# pwr.net
KiCad netlist of a schematic drawn in EAGLE
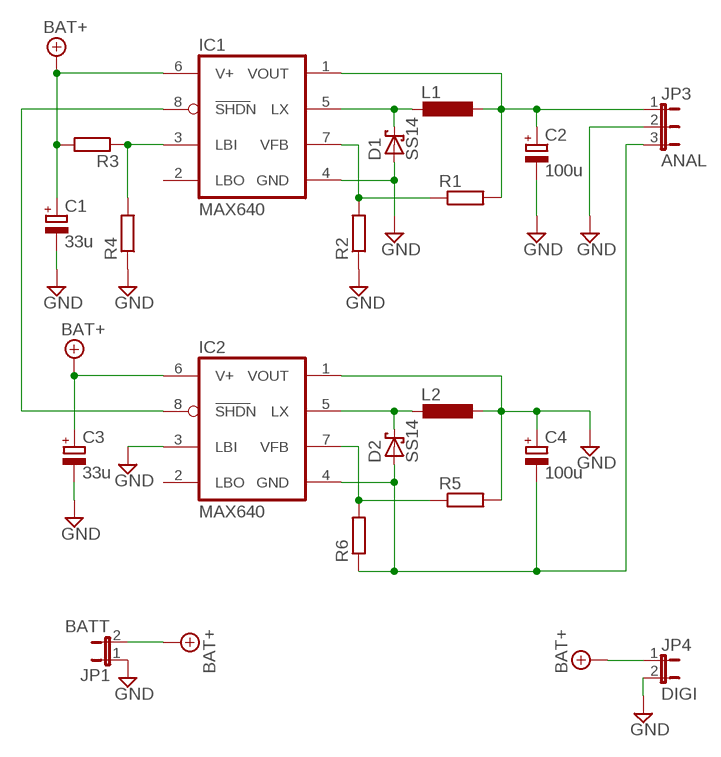
[diagram p0: schematic, sheet 1]

(export (version "E")
  (design (tool "Eeschema 10.0.6"))
  (components
    (comp (ref "C1")
      (value "33u")
      (footprint "eagle-import:SMC_C")
      (libsource (lib "eagle-import") (part "CPOL-EUSMCC"))
    )
    (comp (ref "C2")
      (value "100u")
      (footprint "eagle-import:SMC_C")
      (libsource (lib "eagle-import") (part "CPOL-EUSMCC"))
    )
    (comp (ref "C3")
      (value "33u")
      (footprint "eagle-import:SMC_C")
      (libsource (lib "eagle-import") (part "CPOL-EUSMCC"))
    )
    (comp (ref "C4")
      (value "100u")
      (footprint "eagle-import:SMC_C")
      (libsource (lib "eagle-import") (part "CPOL-EUSMCC"))
    )
    (comp (ref "D1")
      (value "SS14")
      (footprint "eagle-import:SMA")
      (libsource (lib "eagle-import") (part "SS14"))
    )
    (comp (ref "D2")
      (value "SS14")
      (footprint "eagle-import:SMA")
      (libsource (lib "eagle-import") (part "SS14"))
    )
    (comp (ref "IC1")
      (value "MAX640")
      (footprint "eagle-import:SO08")
      (libsource (lib "eagle-import") (part "MAX640"))
    )
    (comp (ref "IC2")
      (value "MAX640")
      (footprint "eagle-import:SO08")
      (libsource (lib "eagle-import") (part "MAX640"))
    )
    (comp (ref "JP1")
      (value "BATT")
      (footprint "eagle-import:JP1")
      (libsource (lib "eagle-import") (part "JP1E"))
    )
    (comp (ref "JP3")
      (value "ANAL")
      (footprint "eagle-import:JP2")
      (libsource (lib "eagle-import") (part "JP2E"))
    )
    (comp (ref "JP4")
      (value "DIGI")
      (footprint "eagle-import:JP1")
      (libsource (lib "eagle-import") (part "JP1E"))
    )
    (comp (ref "L1")
      (value "L-EUWE-TPC")
      (footprint "eagle-import:POWER-CHOKE_WE-TPC")
      (libsource (lib "eagle-import") (part "L-EUWE-TPC"))
    )
    (comp (ref "L2")
      (value "L-EUWE-TPC")
      (footprint "eagle-import:POWER-CHOKE_WE-TPC")
      (libsource (lib "eagle-import") (part "L-EUWE-TPC"))
    )
    (comp (ref "R1")
      (value "R-EU_R0805")
      (footprint "eagle-import:R0805")
      (libsource (lib "eagle-import") (part "R-EU_R0805"))
    )
    (comp (ref "R2")
      (value "R-EU_R0805")
      (footprint "eagle-import:R0805")
      (libsource (lib "eagle-import") (part "R-EU_R0805"))
    )
    (comp (ref "R3")
      (value "R-EU_R0805")
      (footprint "eagle-import:R0805")
      (libsource (lib "eagle-import") (part "R-EU_R0805"))
    )
    (comp (ref "R4")
      (value "R-EU_R0805")
      (footprint "eagle-import:R0805")
      (libsource (lib "eagle-import") (part "R-EU_R0805"))
    )
    (comp (ref "R5")
      (value "R-EU_R0805")
      (footprint "eagle-import:R0805")
      (libsource (lib "eagle-import") (part "R-EU_R0805"))
    )
    (comp (ref "R6")
      (value "R-EU_R0805")
      (footprint "eagle-import:R0805")
      (libsource (lib "eagle-import") (part "R-EU_R0805"))
    )
  )
  (nets
    (net (code "1") (name "BAT+") (class "Default")
      (node (ref "C1") (pin "+") (pinfunction "+_+") (pintype "passive"))
      (node (ref "C3") (pin "+") (pinfunction "+_+") (pintype "passive"))
      (node (ref "IC1") (pin "6") (pinfunction "V+_6") (pintype "power_in"))
      (node (ref "IC2") (pin "6") (pinfunction "V+_6") (pintype "power_in"))
      (node (ref "JP1") (pin "2") (pinfunction "2_2") (pintype "passive"))
      (node (ref "JP4") (pin "1") (pinfunction "1_1") (pintype "passive"))
      (node (ref "R3") (pin "2") (pinfunction "2_2") (pintype "passive"))
    )
    (net (code "2") (name "GND") (class "Default")
      (node (ref "C1") (pin "-") (pinfunction "-_-") (pintype "passive"))
      (node (ref "C2") (pin "-") (pinfunction "-_-") (pintype "passive"))
      (node (ref "C3") (pin "-") (pinfunction "-_-") (pintype "passive"))
      (node (ref "C4") (pin "+") (pinfunction "+_+") (pintype "passive"))
      (node (ref "D1") (pin "A") (pinfunction "A_A") (pintype "passive"))
      (node (ref "IC1") (pin "4") (pinfunction "GND_4") (pintype "power_in"))
      (node (ref "IC2") (pin "1") (pinfunction "VOUT_1") (pintype "output"))
      (node (ref "IC2") (pin "3") (pinfunction "LBI_3") (pintype "input"))
      (node (ref "JP1") (pin "1") (pinfunction "1_1") (pintype "passive"))
      (node (ref "JP3") (pin "2") (pinfunction "2_2") (pintype "passive"))
      (node (ref "JP4") (pin "2") (pinfunction "2_2") (pintype "passive"))
      (node (ref "L2") (pin "1") (pinfunction "1_1") (pintype "passive"))
      (node (ref "R2") (pin "1") (pinfunction "1_1") (pintype "passive"))
      (node (ref "R4") (pin "1") (pinfunction "1_1") (pintype "passive"))
      (node (ref "R5") (pin "2") (pinfunction "2_2") (pintype "passive"))
    )
    (net (code "3") (name "Net-(IC1-LBI)") (class "Default")
      (node (ref "IC1") (pin "3") (pinfunction "LBI_3") (pintype "input"))
      (node (ref "R3") (pin "1") (pinfunction "1_1") (pintype "passive"))
      (node (ref "R4") (pin "2") (pinfunction "2_2") (pintype "passive"))
    )
    (net (code "4") (name "Net-(IC1-LX)") (class "Default")
      (node (ref "D1") (pin "C") (pinfunction "C_C") (pintype "passive"))
      (node (ref "IC1") (pin "5") (pinfunction "LX_5") (pintype "output"))
      (node (ref "L1") (pin "2") (pinfunction "2_2") (pintype "passive"))
    )
    (net (code "5") (name "Net-(IC1-SHDN)") (class "Default")
      (node (ref "IC1") (pin "8") (pinfunction "SHDN_8") (pintype "input"))
      (node (ref "IC2") (pin "8") (pinfunction "SHDN_8") (pintype "input"))
    )
    (net (code "6") (name "Net-(IC1-VFB)") (class "Default")
      (node (ref "IC1") (pin "7") (pinfunction "VFB_7") (pintype "output"))
      (node (ref "R1") (pin "1") (pinfunction "1_1") (pintype "passive"))
      (node (ref "R2") (pin "2") (pinfunction "2_2") (pintype "passive"))
    )
    (net (code "7") (name "Net-(IC1-VOUT)") (class "Default")
      (node (ref "C2") (pin "+") (pinfunction "+_+") (pintype "passive"))
      (node (ref "IC1") (pin "1") (pinfunction "VOUT_1") (pintype "output"))
      (node (ref "JP3") (pin "1") (pinfunction "1_1") (pintype "passive"))
      (node (ref "L1") (pin "1") (pinfunction "1_1") (pintype "passive"))
      (node (ref "R1") (pin "2") (pinfunction "2_2") (pintype "passive"))
    )
    (net (code "8") (name "Net-(IC2-GND)") (class "Default")
      (node (ref "C4") (pin "-") (pinfunction "-_-") (pintype "passive"))
      (node (ref "D2") (pin "A") (pinfunction "A_A") (pintype "passive"))
      (node (ref "IC2") (pin "4") (pinfunction "GND_4") (pintype "power_in"))
      (node (ref "JP3") (pin "3") (pinfunction "3_3") (pintype "passive"))
      (node (ref "R6") (pin "1") (pinfunction "1_1") (pintype "passive"))
    )
    (net (code "9") (name "Net-(IC2-LX)") (class "Default")
      (node (ref "D2") (pin "C") (pinfunction "C_C") (pintype "passive"))
      (node (ref "IC2") (pin "5") (pinfunction "LX_5") (pintype "output"))
      (node (ref "L2") (pin "2") (pinfunction "2_2") (pintype "passive"))
    )
    (net (code "10") (name "Net-(IC2-VFB)") (class "Default")
      (node (ref "IC2") (pin "7") (pinfunction "VFB_7") (pintype "output"))
      (node (ref "R5") (pin "1") (pinfunction "1_1") (pintype "passive"))
      (node (ref "R6") (pin "2") (pinfunction "2_2") (pintype "passive"))
    )
    (net (code "11") (name "unconnected-(IC1-LBO-Pad2)") (class "Default")
      (node (ref "IC1") (pin "2") (pinfunction "LBO_2") (pintype "output"))
    )
    (net (code "12") (name "unconnected-(IC2-LBO-Pad2)") (class "Default")
      (node (ref "IC2") (pin "2") (pinfunction "LBO_2") (pintype "output"))
    )
  )
)
